# chess_module_LEDs.net
KiCad netlist of a schematic drawn in Altium Designer
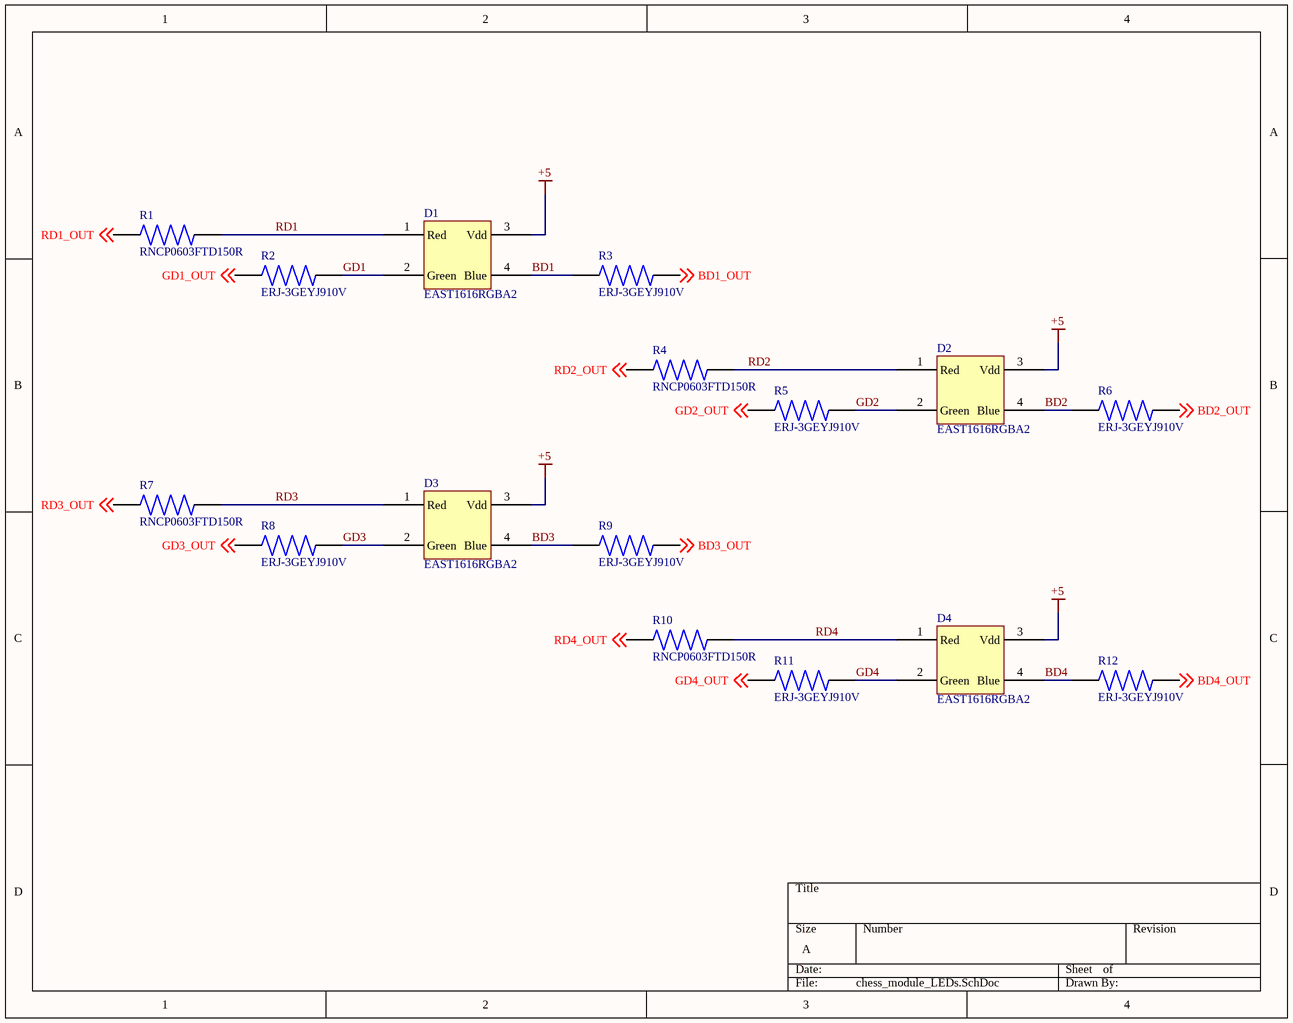
[diagram p0: chess_module_LEDs.SchDoc]

(export (version "E")
  (design (tool "Eeschema 10.0.6"))
  (components
    (comp (ref "D1")
      (value "EAST1616RGBA2")
      (footprint "EAST1616RGBA2")
      (libsource (lib "chess_module") (part "EAST1616RGBA2"))
    )
    (comp (ref "D2")
      (value "EAST1616RGBA2")
      (footprint "EAST1616RGBA2")
      (libsource (lib "chess_module") (part "EAST1616RGBA2"))
    )
    (comp (ref "D3")
      (value "EAST1616RGBA2")
      (footprint "EAST1616RGBA2")
      (libsource (lib "chess_module") (part "EAST1616RGBA2"))
    )
    (comp (ref "D4")
      (value "EAST1616RGBA2")
      (footprint "EAST1616RGBA2")
      (libsource (lib "chess_module") (part "EAST1616RGBA2"))
    )
    (comp (ref "R1")
      (value "RNCP0603FTD150R")
      (footprint "RESC1508X50N:RESC1508X50N")
      (libsource (lib "chess_module") (part "RNCP0603FTD150R"))
    )
    (comp (ref "R2")
      (value "ERJ-3GEYJ910V")
      (footprint "RESC1608X55N:RESC1608X55N")
      (description "Res Thick Film 0603 91 Ohm 5% 1/10W Ã‚Â±200ppm/Ã‚Â°C Molded SMD SMD Punched Carrier T/R")
      (libsource (lib "chess_module") (part "ERJ-3GEYJ910V"))
    )
    (comp (ref "R3")
      (value "ERJ-3GEYJ910V")
      (footprint "RESC1608X55N:RESC1608X55N")
      (description "Res Thick Film 0603 91 Ohm 5% 1/10W Ã‚Â±200ppm/Ã‚Â°C Molded SMD SMD Punched Carrier T/R")
      (libsource (lib "chess_module") (part "ERJ-3GEYJ910V"))
    )
    (comp (ref "R4")
      (value "RNCP0603FTD150R")
      (footprint "RESC1508X50N:RESC1508X50N")
      (libsource (lib "chess_module") (part "RNCP0603FTD150R"))
    )
    (comp (ref "R5")
      (value "ERJ-3GEYJ910V")
      (footprint "RESC1608X55N:RESC1608X55N")
      (description "Res Thick Film 0603 91 Ohm 5% 1/10W Ã‚Â±200ppm/Ã‚Â°C Molded SMD SMD Punched Carrier T/R")
      (libsource (lib "chess_module") (part "ERJ-3GEYJ910V"))
    )
    (comp (ref "R6")
      (value "ERJ-3GEYJ910V")
      (footprint "RESC1608X55N:RESC1608X55N")
      (description "Res Thick Film 0603 91 Ohm 5% 1/10W Ã‚Â±200ppm/Ã‚Â°C Molded SMD SMD Punched Carrier T/R")
      (libsource (lib "chess_module") (part "ERJ-3GEYJ910V"))
    )
    (comp (ref "R7")
      (value "RNCP0603FTD150R")
      (footprint "RESC1508X50N:RESC1508X50N")
      (libsource (lib "chess_module") (part "RNCP0603FTD150R"))
    )
    (comp (ref "R8")
      (value "ERJ-3GEYJ910V")
      (footprint "RESC1608X55N:RESC1608X55N")
      (description "Res Thick Film 0603 91 Ohm 5% 1/10W Ã‚Â±200ppm/Ã‚Â°C Molded SMD SMD Punched Carrier T/R")
      (libsource (lib "chess_module") (part "ERJ-3GEYJ910V"))
    )
    (comp (ref "R9")
      (value "ERJ-3GEYJ910V")
      (footprint "RESC1608X55N:RESC1608X55N")
      (description "Res Thick Film 0603 91 Ohm 5% 1/10W Ã‚Â±200ppm/Ã‚Â°C Molded SMD SMD Punched Carrier T/R")
      (libsource (lib "chess_module") (part "ERJ-3GEYJ910V"))
    )
    (comp (ref "R10")
      (value "RNCP0603FTD150R")
      (footprint "RESC1508X50N:RESC1508X50N")
      (libsource (lib "chess_module") (part "RNCP0603FTD150R"))
    )
    (comp (ref "R11")
      (value "ERJ-3GEYJ910V")
      (footprint "RESC1608X55N:RESC1608X55N")
      (description "Res Thick Film 0603 91 Ohm 5% 1/10W Ã‚Â±200ppm/Ã‚Â°C Molded SMD SMD Punched Carrier T/R")
      (libsource (lib "chess_module") (part "ERJ-3GEYJ910V"))
    )
    (comp (ref "R12")
      (value "ERJ-3GEYJ910V")
      (footprint "RESC1608X55N:RESC1608X55N")
      (description "Res Thick Film 0603 91 Ohm 5% 1/10W Ã‚Â±200ppm/Ã‚Â°C Molded SMD SMD Punched Carrier T/R")
      (libsource (lib "chess_module") (part "ERJ-3GEYJ910V"))
    )
  )
  (nets
    (net (code "1") (name "+5") (class "Default")
      (node (ref "D1") (pin "3") (pinfunction "Vdd_3") (pintype "passive"))
      (node (ref "D2") (pin "3") (pinfunction "Vdd_3") (pintype "passive"))
      (node (ref "D3") (pin "3") (pinfunction "Vdd_3") (pintype "passive"))
      (node (ref "D4") (pin "3") (pinfunction "Vdd_3") (pintype "passive"))
    )
    (net (code "2") (name "/BD1") (class "Default")
      (node (ref "D1") (pin "4") (pinfunction "Blue_4") (pintype "passive"))
      (node (ref "R3") (pin "2") (pinfunction "2_2") (pintype "passive"))
    )
    (net (code "3") (name "/BD2") (class "Default")
      (node (ref "D2") (pin "4") (pinfunction "Blue_4") (pintype "passive"))
      (node (ref "R6") (pin "2") (pinfunction "2_2") (pintype "passive"))
    )
    (net (code "4") (name "/BD3") (class "Default")
      (node (ref "D3") (pin "4") (pinfunction "Blue_4") (pintype "passive"))
      (node (ref "R9") (pin "2") (pinfunction "2_2") (pintype "passive"))
    )
    (net (code "5") (name "/BD4") (class "Default")
      (node (ref "D4") (pin "4") (pinfunction "Blue_4") (pintype "passive"))
      (node (ref "R12") (pin "1") (pinfunction "1_1") (pintype "passive"))
    )
    (net (code "6") (name "/GD1") (class "Default")
      (node (ref "D1") (pin "2") (pinfunction "Green_2") (pintype "passive"))
      (node (ref "R2") (pin "2") (pinfunction "2_2") (pintype "passive"))
    )
    (net (code "7") (name "/GD2") (class "Default")
      (node (ref "D2") (pin "2") (pinfunction "Green_2") (pintype "passive"))
      (node (ref "R5") (pin "2") (pinfunction "2_2") (pintype "passive"))
    )
    (net (code "8") (name "/GD3") (class "Default")
      (node (ref "D3") (pin "2") (pinfunction "Green_2") (pintype "passive"))
      (node (ref "R8") (pin "1") (pinfunction "1_1") (pintype "passive"))
    )
    (net (code "9") (name "/GD4") (class "Default")
      (node (ref "D4") (pin "2") (pinfunction "Green_2") (pintype "passive"))
      (node (ref "R11") (pin "2") (pinfunction "2_2") (pintype "passive"))
    )
    (net (code "10") (name "/RD1") (class "Default")
      (node (ref "D1") (pin "1") (pinfunction "Red_1") (pintype "passive"))
      (node (ref "R1") (pin "2") (pinfunction "2_2") (pintype "passive"))
    )
    (net (code "11") (name "/RD2") (class "Default")
      (node (ref "D2") (pin "1") (pinfunction "Red_1") (pintype "passive"))
      (node (ref "R4") (pin "2") (pinfunction "2_2") (pintype "passive"))
    )
    (net (code "12") (name "/RD3") (class "Default")
      (node (ref "D3") (pin "1") (pinfunction "Red_1") (pintype "passive"))
      (node (ref "R7") (pin "1") (pinfunction "1_1") (pintype "passive"))
    )
    (net (code "13") (name "/RD4") (class "Default")
      (node (ref "D4") (pin "1") (pinfunction "Red_1") (pintype "passive"))
      (node (ref "R10") (pin "2") (pinfunction "2_2") (pintype "passive"))
    )
    (net (code "14") (name "BD1_OUT") (class "Default")
      (node (ref "R3") (pin "1") (pinfunction "1_1") (pintype "passive"))
    )
    (net (code "15") (name "BD2_OUT") (class "Default")
      (node (ref "R6") (pin "1") (pinfunction "1_1") (pintype "passive"))
    )
    (net (code "16") (name "BD3_OUT") (class "Default")
      (node (ref "R9") (pin "1") (pinfunction "1_1") (pintype "passive"))
    )
    (net (code "17") (name "BD4_OUT") (class "Default")
      (node (ref "R12") (pin "2") (pinfunction "2_2") (pintype "passive"))
    )
    (net (code "18") (name "GD1_OUT") (class "Default")
      (node (ref "R2") (pin "1") (pinfunction "1_1") (pintype "passive"))
    )
    (net (code "19") (name "GD2_OUT") (class "Default")
      (node (ref "R5") (pin "1") (pinfunction "1_1") (pintype "passive"))
    )
    (net (code "20") (name "GD3_OUT") (class "Default")
      (node (ref "R8") (pin "2") (pinfunction "2_2") (pintype "passive"))
    )
    (net (code "21") (name "GD4_OUT") (class "Default")
      (node (ref "R11") (pin "1") (pinfunction "1_1") (pintype "passive"))
    )
    (net (code "22") (name "RD1_OUT") (class "Default")
      (node (ref "R1") (pin "1") (pinfunction "1_1") (pintype "passive"))
    )
    (net (code "23") (name "RD2_OUT") (class "Default")
      (node (ref "R4") (pin "1") (pinfunction "1_1") (pintype "passive"))
    )
    (net (code "24") (name "RD3_OUT") (class "Default")
      (node (ref "R7") (pin "2") (pinfunction "2_2") (pintype "passive"))
    )
    (net (code "25") (name "RD4_OUT") (class "Default")
      (node (ref "R10") (pin "1") (pinfunction "1_1") (pintype "passive"))
    )
  )
)
